# power_supply_5v_3_3v_v11_othermill.net
KiCad netlist of a schematic drawn in EAGLE
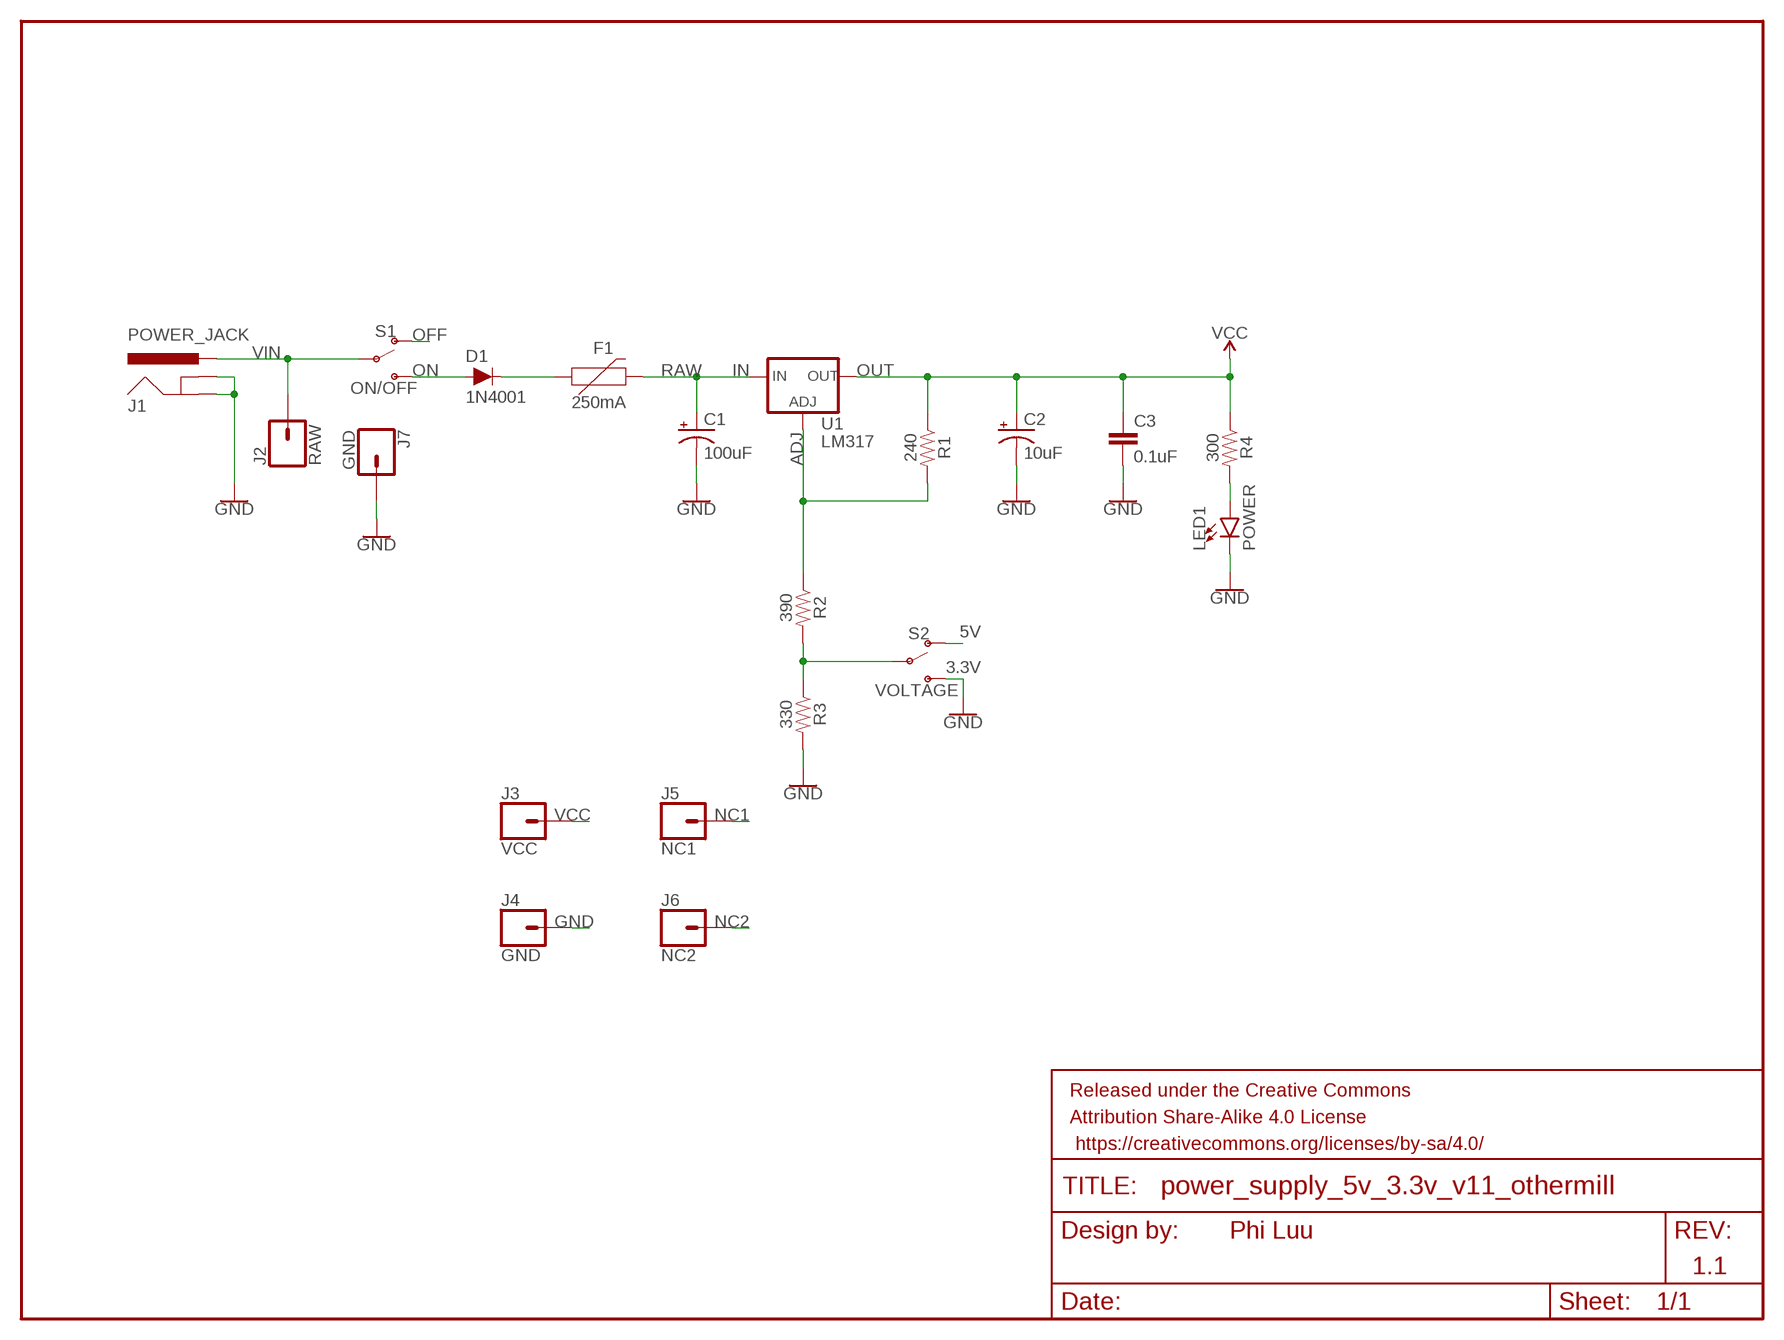
[diagram p0: schematic, sheet 1]

(export (version "E")
  (design (tool "Eeschema 10.0.6"))
  (components
    (comp (ref "C1")
      (value "100uF")
      (footprint "eagle-import:CPOL-RADIAL-2.5MM-6.5MM")
      (libsource (lib "eagle-import") (part "100UF-POLAR-RADIAL-2.5MM-25V-20%"))
    )
    (comp (ref "C2")
      (value "10uF")
      (footprint "eagle-import:CPOL-RADIAL-2.5MM-5MM")
      (libsource (lib "eagle-import") (part "10UF-POLAR-RADIAL-2.5MM-25V-20%"))
    )
    (comp (ref "C3")
      (value "0.1uF")
      (footprint "eagle-import:CAP-PTH-SMALL-KIT")
      (libsource (lib "eagle-import") (part "0.1UF-KIT-EZ-50V-20%"))
    )
    (comp (ref "D1")
      (value "1N4001")
      (footprint "eagle-import:DIODE-1N4001")
      (libsource (lib "eagle-import") (part "DIODE-PTH"))
    )
    (comp (ref "F1")
      (value "250mA")
      (footprint "eagle-import:PTH")
      (libsource (lib "eagle-import") (part "PPTC_PTH"))
    )
    (comp (ref "FRAME1")
      (value "FRAME-LETTER")
      (footprint "eagle-import:CREATIVE_COMMONS")
      (libsource (lib "eagle-import") (part "FRAME-LETTER"))
    )
    (comp (ref "J1")
      (value "POWER_JACK")
      (footprint "eagle-import:POWER_JACK_PTH")
      (libsource (lib "eagle-import") (part "POWER_JACK"))
    )
    (comp (ref "J2")
      (value "RAW")
      (footprint "eagle-import:1X01")
      (libsource (lib "eagle-import") (part "CONN_01"))
    )
    (comp (ref "J3")
      (value "VCC")
      (footprint "eagle-import:1X01")
      (libsource (lib "eagle-import") (part "CONN_01"))
    )
    (comp (ref "J4")
      (value "GND")
      (footprint "eagle-import:1X01")
      (libsource (lib "eagle-import") (part "CONN_01"))
    )
    (comp (ref "J5")
      (value "NC1")
      (footprint "eagle-import:1X01")
      (libsource (lib "eagle-import") (part "CONN_01"))
    )
    (comp (ref "J6")
      (value "NC2")
      (footprint "eagle-import:1X01")
      (libsource (lib "eagle-import") (part "CONN_01"))
    )
    (comp (ref "J7")
      (value "GND")
      (footprint "eagle-import:1X01")
      (libsource (lib "eagle-import") (part "CONN_01"))
    )
    (comp (ref "LED1")
      (value "POWER")
      (footprint "eagle-import:LED_5MM")
      (libsource (lib "eagle-import") (part "LED5MM"))
    )
    (comp (ref "R1")
      (value "240")
      (footprint "eagle-import:AXIAL-0.3")
      (libsource (lib "eagle-import") (part "1KOHM-HORIZ-1/4W-5%"))
    )
    (comp (ref "R2")
      (value "390")
      (footprint "eagle-import:AXIAL-0.3")
      (libsource (lib "eagle-import") (part "1KOHM-HORIZ-1/4W-5%"))
    )
    (comp (ref "R3")
      (value "330")
      (footprint "eagle-import:AXIAL-0.3")
      (libsource (lib "eagle-import") (part "1KOHM-HORIZ-1/4W-5%"))
    )
    (comp (ref "R4")
      (value "300")
      (footprint "eagle-import:AXIAL-0.3")
      (libsource (lib "eagle-import") (part "1KOHM-HORIZ-1/4W-5%"))
    )
    (comp (ref "S1")
      (value "ON/OFF")
      (footprint "eagle-import:SWITCH_SPDT_PTH_11.6X4.0MM")
      (libsource (lib "eagle-import") (part "SWITCH-SPDT-PTH-11.6X4.0MM"))
    )
    (comp (ref "S2")
      (value "VOLTAGE")
      (footprint "eagle-import:SWITCH_SPDT_PTH_11.6X4.0MM")
      (libsource (lib "eagle-import") (part "SWITCH-SPDT-PTH-11.6X4.0MM"))
    )
    (comp (ref "U1")
      (value "LM317")
      (footprint "eagle-import:TO220-ADJ")
      (libsource (lib "eagle-import") (part "V_REG_317SINK"))
    )
  )
  (nets
    (net (code "1") (name "/5V") (class "Default")
      (node (ref "S2") (pin "1") (pinfunction "O_1") (pintype "passive"))
    )
    (net (code "2") (name "/ADJ") (class "Default")
      (node (ref "R1") (pin "P$2") (pinfunction "2_P$2") (pintype "passive"))
      (node (ref "R2") (pin "P$1") (pinfunction "1_P$1") (pintype "passive"))
      (node (ref "U1") (pin "ADJ") (pinfunction "ADJ_ADJ") (pintype "input"))
    )
    (net (code "3") (name "/NC1") (class "Default")
      (node (ref "J5") (pin "1") (pinfunction "1_1") (pintype "passive"))
    )
    (net (code "4") (name "/NC2") (class "Default")
      (node (ref "J6") (pin "1") (pinfunction "1_1") (pintype "passive"))
    )
    (net (code "5") (name "/OFF") (class "Default")
      (node (ref "S1") (pin "1") (pinfunction "O_1") (pintype "passive"))
    )
    (net (code "6") (name "/ON") (class "Default")
      (node (ref "D1") (pin "A") (pinfunction "A_A") (pintype "passive"))
      (node (ref "S1") (pin "3") (pinfunction "S_3") (pintype "passive"))
    )
    (net (code "7") (name "/RAW") (class "Default")
      (node (ref "C1") (pin "1") (pinfunction "+_1") (pintype "passive"))
      (node (ref "F1") (pin "P$2") (pinfunction "2_P$2") (pintype "bidirectional"))
      (node (ref "U1") (pin "IN") (pinfunction "IN_IN") (pintype "input"))
    )
    (net (code "8") (name "/VIN") (class "Default")
      (node (ref "J1") (pin "PWR") (pinfunction "PWR_PWR") (pintype "bidirectional"))
      (node (ref "J2") (pin "1") (pinfunction "1_1") (pintype "passive"))
      (node (ref "S1") (pin "2") (pinfunction "P_2") (pintype "passive"))
    )
    (net (code "9") (name "GND") (class "Default")
      (node (ref "C1") (pin "2") (pinfunction "-_2") (pintype "passive"))
      (node (ref "C2") (pin "2") (pinfunction "-_2") (pintype "passive"))
      (node (ref "C3") (pin "2") (pinfunction "2_2") (pintype "passive"))
      (node (ref "J1") (pin "GND") (pinfunction "GND_GND") (pintype "bidirectional"))
      (node (ref "J1") (pin "GNDBREAK") (pinfunction "GNDBREAK_GNDBREAK") (pintype "bidirectional"))
      (node (ref "J4") (pin "1") (pinfunction "1_1") (pintype "passive"))
      (node (ref "J7") (pin "1") (pinfunction "1_1") (pintype "passive"))
      (node (ref "LED1") (pin "K") (pinfunction "C_K") (pintype "passive"))
      (node (ref "R3") (pin "P$2") (pinfunction "2_P$2") (pintype "passive"))
      (node (ref "S2") (pin "3") (pinfunction "S_3") (pintype "passive"))
    )
    (net (code "10") (name "Net-(F1-1)") (class "Default")
      (node (ref "D1") (pin "C") (pinfunction "C_C") (pintype "passive"))
      (node (ref "F1") (pin "P$1") (pinfunction "1_P$1") (pintype "bidirectional"))
    )
    (net (code "11") (name "Net-(R2-2)") (class "Default")
      (node (ref "R2") (pin "P$2") (pinfunction "2_P$2") (pintype "passive"))
      (node (ref "R3") (pin "P$1") (pinfunction "1_P$1") (pintype "passive"))
      (node (ref "S2") (pin "2") (pinfunction "P_2") (pintype "passive"))
    )
    (net (code "12") (name "Net-(R4-2)") (class "Default")
      (node (ref "LED1") (pin "A") (pinfunction "A_A") (pintype "passive"))
      (node (ref "R4") (pin "P$2") (pinfunction "2_P$2") (pintype "passive"))
    )
    (net (code "13") (name "VCC") (class "Default")
      (node (ref "C2") (pin "1") (pinfunction "+_1") (pintype "passive"))
      (node (ref "C3") (pin "1") (pinfunction "1_1") (pintype "passive"))
      (node (ref "J3") (pin "1") (pinfunction "1_1") (pintype "passive"))
      (node (ref "R1") (pin "P$1") (pinfunction "1_P$1") (pintype "passive"))
      (node (ref "R4") (pin "P$1") (pinfunction "1_P$1") (pintype "passive"))
      (node (ref "U1") (pin "OUT") (pinfunction "OUT_OUT") (pintype "output"))
    )
  )
)
